# Sch_Kur.net
KiCad netlist of a schematic drawn in Altium Designer
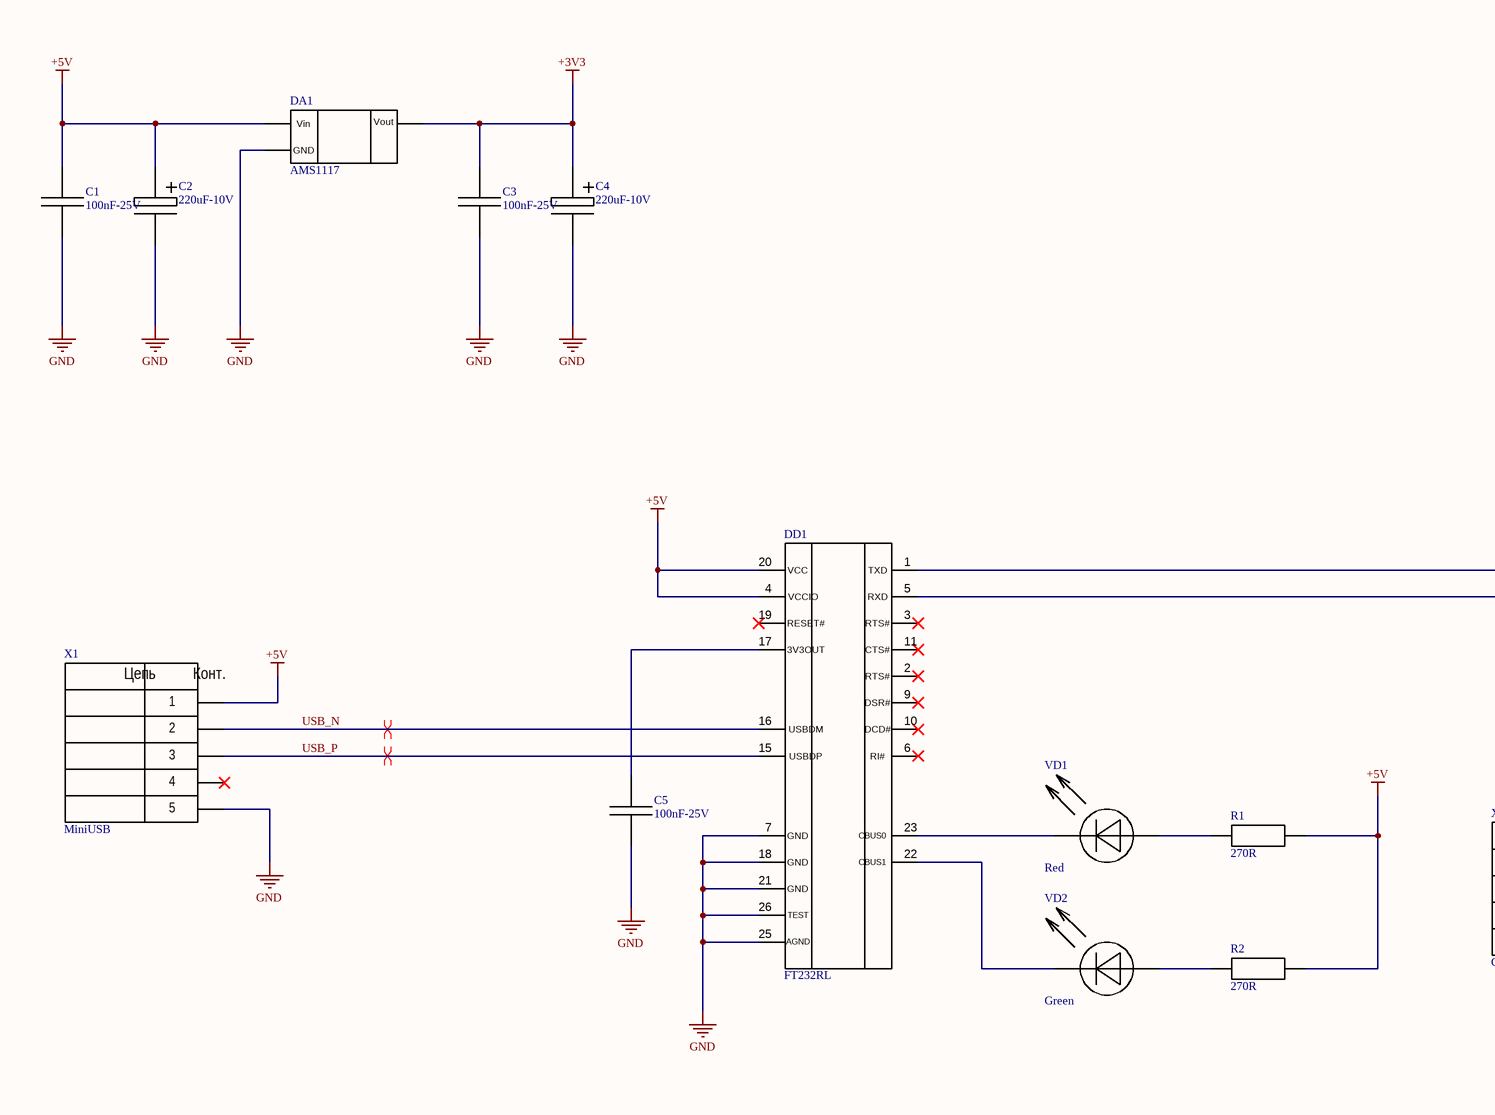
[diagram p0: Sch_Kur.SchDoc, left]
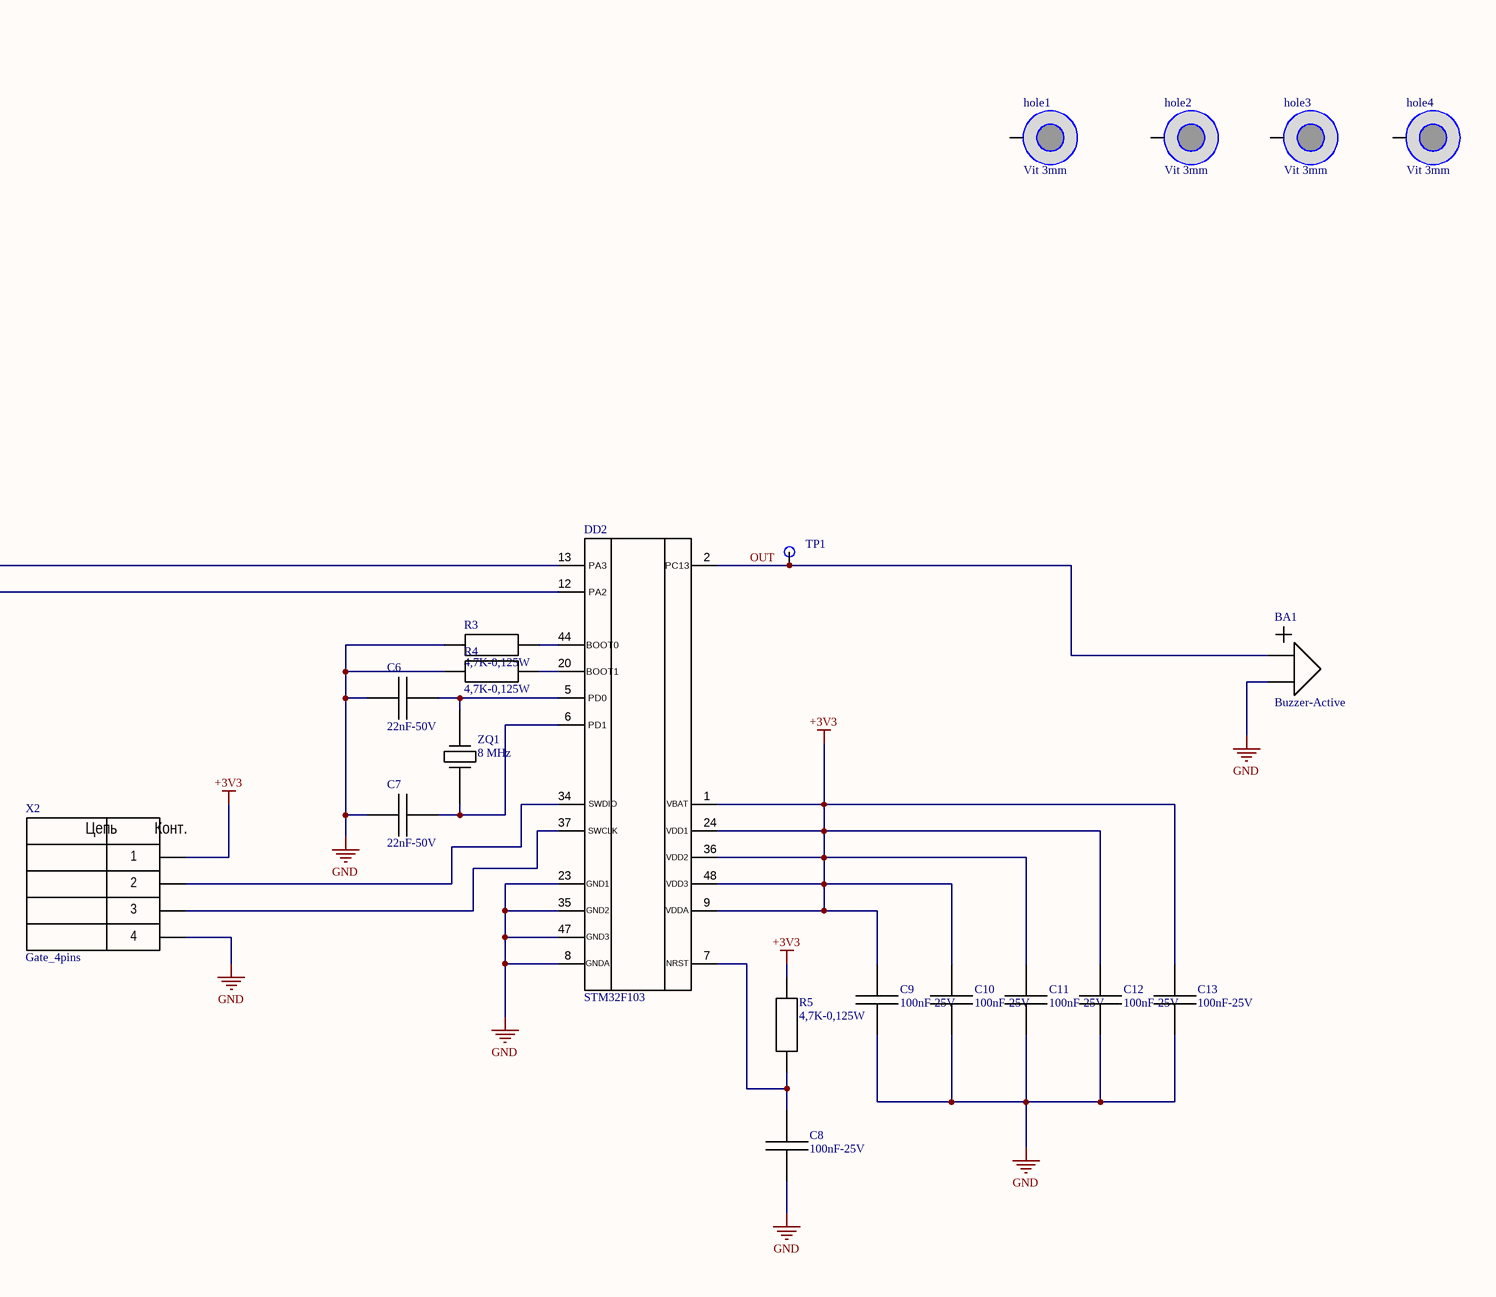
[diagram p1: Sch_Kur.SchDoc, right]

(export (version "E")
  (design (tool "Eeschema 10.0.6"))
  (components
    (comp (ref "BA1")
      (value "Buzzer-Active")
      (footprint "28# Buzzer MINI")
      (libsource (lib "Schlib_Kur") (part "Buzzer"))
    )
    (comp (ref "C1")
      (value "100nF-25V")
      (footprint "Cap Ceramic 0603 SMD")
      (libsource (lib "Schlib_Kur") (part "Cap_100nF"))
    )
    (comp (ref "C2")
      (value "220uF-10V")
      (footprint "CAP ALU CASE E SMD")
      (libsource (lib "Schlib_Kur") (part "ECAP_220uF"))
    )
    (comp (ref "C3")
      (value "100nF-25V")
      (footprint "Cap Ceramic 0603 SMD")
      (libsource (lib "Schlib_Kur") (part "Cap_100nF"))
    )
    (comp (ref "C4")
      (value "220uF-10V")
      (footprint "CAP ALU CASE E SMD")
      (libsource (lib "Schlib_Kur") (part "ECAP_220uF"))
    )
    (comp (ref "C5")
      (value "100nF-25V")
      (footprint "Cap Ceramic 0603 SMD")
      (libsource (lib "Schlib_Kur") (part "Cap_100nF"))
    )
    (comp (ref "C6")
      (value "22nF-50V")
      (footprint "Cap Ceramic 0805 SMD")
      (libsource (lib "Schlib_Kur") (part "Cap_22nF"))
    )
    (comp (ref "C7")
      (value "22nF-50V")
      (footprint "Cap Ceramic 0805 SMD")
      (libsource (lib "Schlib_Kur") (part "Cap_22nF"))
    )
    (comp (ref "C8")
      (value "100nF-25V")
      (footprint "Cap Ceramic 0603 SMD")
      (libsource (lib "Schlib_Kur") (part "Cap_100nF"))
    )
    (comp (ref "C9")
      (value "100nF-25V")
      (footprint "Cap Ceramic 0603 SMD")
      (libsource (lib "Schlib_Kur") (part "Cap_100nF"))
    )
    (comp (ref "C10")
      (value "100nF-25V")
      (footprint "Cap Ceramic 0603 SMD")
      (libsource (lib "Schlib_Kur") (part "Cap_100nF"))
    )
    (comp (ref "C11")
      (value "100nF-25V")
      (footprint "Cap Ceramic 0603 SMD")
      (libsource (lib "Schlib_Kur") (part "Cap_100nF"))
    )
    (comp (ref "C12")
      (value "100nF-25V")
      (footprint "Cap Ceramic 0603 SMD")
      (libsource (lib "Schlib_Kur") (part "Cap_100nF"))
    )
    (comp (ref "C13")
      (value "100nF-25V")
      (footprint "Cap Ceramic 0603 SMD")
      (libsource (lib "Schlib_Kur") (part "Cap_100nF"))
    )
    (comp (ref "DA1")
      (value "AMS1117")
      (footprint "AMS1117-3.3V")
      (libsource (lib "Schlib_Kur") (part "AMS1117-3.3"))
    )
    (comp (ref "DD1") (value "FT232RL") (footprint "SSOP 28") (libsource (lib "Schlib_Kur") (part "FT232RL")))
    (comp (ref "DD2")
      (value "STM32F103")
      (footprint "stm32f103c8t6-48LQFP")
      (libsource (lib "Schlib_Kur") (part "STM32F103C8T6"))
    )
    (comp (ref "hole1")
      (value "Vit 3mm")
      (footprint "Screw 3 small")
      (libsource (lib "lpson") (part "Vit 3mm"))
    )
    (comp (ref "hole2")
      (value "Vit 3mm")
      (footprint "Screw 3 small")
      (libsource (lib "lpson") (part "Vit 3mm"))
    )
    (comp (ref "hole3")
      (value "Vit 3mm")
      (footprint "Screw 3 small")
      (libsource (lib "lpson") (part "Vit 3mm"))
    )
    (comp (ref "hole4")
      (value "Vit 3mm")
      (footprint "Screw 3 small")
      (libsource (lib "lpson") (part "Vit 3mm"))
    )
    (comp (ref "R1") (value "270R") (footprint "Res 0805 SMD") (libsource (lib "") (part "Res_270_1")))
    (comp (ref "R2")
      (value "270R")
      (footprint "Res 0805 SMD")
      (libsource (lib "Schlib_Kur") (part "Res_270"))
    )
    (comp (ref "R3")
      (value "4,7K-0,125W")
      (footprint "Res 0805 SMD")
      (libsource (lib "Schlib_Kur") (part "Res_4K7"))
    )
    (comp (ref "R4")
      (value "4,7K-0,125W")
      (footprint "Res 0805 SMD")
      (libsource (lib "Schlib_Kur") (part "Res_4K7"))
    )
    (comp (ref "R5")
      (value "4,7K-0,125W")
      (footprint "Res 0805 SMD")
      (libsource (lib "Schlib_Kur") (part "Res_4K7"))
    )
    (comp (ref "TP1") (value "TP1") (footprint "TP1") (libsource (lib "Schlib_Kur") (part "Test_point")))
    (comp (ref "VD1") (value "Red") (footprint "Led 0805R") (libsource (lib "Schlib_Kur") (part "LED_red")))
    (comp (ref "VD2")
      (value "Green")
      (footprint "Led 0805G")
      (libsource (lib "Schlib_Kur") (part "LED_green"))
    )
    (comp (ref "X1")
      (value "MiniUSB")
      (footprint "USB_MNI_B")
      (libsource (lib "Schlib_Kur") (part "Mini_USB"))
    )
    (comp (ref "X2")
      (value "Gate_4pins")
      (footprint "Header_4")
      (libsource (lib "Schlib_Kur") (part "Gate_4pins"))
    )
    (comp (ref "ZQ1")
      (value "8 MHz")
      (footprint "CRYSTAL-HC49S")
      (libsource (lib "Schlib_Kur") (part "Quartz resonator_8MHz"))
    )
  )
  (nets
    (net (code "1") (name "+3V3") (class "Default")
      (node (ref "C10") (pin "2") (pinfunction "2_2") (pintype "passive"))
      (node (ref "C11") (pin "2") (pinfunction "2_2") (pintype "passive"))
      (node (ref "C12") (pin "2") (pinfunction "2_2") (pintype "passive"))
      (node (ref "C13") (pin "2") (pinfunction "2_2") (pintype "passive"))
      (node (ref "C3") (pin "2") (pinfunction "2_2") (pintype "passive"))
      (node (ref "C4") (pin "1") (pinfunction "1_1") (pintype "passive"))
      (node (ref "C9") (pin "2") (pinfunction "2_2") (pintype "passive"))
      (node (ref "DA1") (pin "2") (pinfunction "2_2") (pintype "passive"))
      (node (ref "DD2") (pin "1") (pinfunction "1_1") (pintype "passive"))
      (node (ref "DD2") (pin "24") (pinfunction "24_24") (pintype "passive"))
      (node (ref "DD2") (pin "36") (pinfunction "36_36") (pintype "passive"))
      (node (ref "DD2") (pin "48") (pinfunction "48_48") (pintype "passive"))
      (node (ref "DD2") (pin "9") (pinfunction "9_9") (pintype "passive"))
      (node (ref "R5") (pin "2") (pinfunction "2_2") (pintype "passive"))
      (node (ref "X2") (pin "1") (pintype "passive"))
    )
    (net (code "2") (name "+5V") (class "Default")
      (node (ref "C1") (pin "2") (pinfunction "2_2") (pintype "passive"))
      (node (ref "C2") (pin "1") (pinfunction "1_1") (pintype "passive"))
      (node (ref "DA1") (pin "3") (pinfunction "3_3") (pintype "passive"))
      (node (ref "DD1") (pin "20") (pinfunction "20_20") (pintype "passive"))
      (node (ref "DD1") (pin "4") (pinfunction "4_4") (pintype "passive"))
      (node (ref "R1") (pin "2") (pinfunction "2_2") (pintype "passive"))
      (node (ref "R2") (pin "1") (pinfunction "1_1") (pintype "passive"))
      (node (ref "X1") (pin "1") (pinfunction "1_1") (pintype "passive"))
    )
    (net (code "3") (name "/OUT") (class "Default")
      (node (ref "BA1") (pin "1") (pinfunction "1_1") (pintype "passive"))
      (node (ref "DD2") (pin "2") (pinfunction "2_2") (pintype "passive"))
      (node (ref "TP1") (pin "1") (pinfunction "1_1") (pintype "passive"))
    )
    (net (code "4") (name "/USB_N") (class "Default")
      (node (ref "DD1") (pin "16") (pinfunction "16_16") (pintype "passive"))
      (node (ref "X1") (pin "2") (pinfunction "2_2") (pintype "passive"))
    )
    (net (code "5") (name "/USB_P") (class "Default")
      (node (ref "DD1") (pin "15") (pinfunction "15_15") (pintype "passive"))
      (node (ref "X1") (pin "3") (pinfunction "3_3") (pintype "passive"))
    )
    (net (code "6") (name "GND") (class "Default")
      (node (ref "BA1") (pin "2") (pinfunction "2_2") (pintype "passive"))
      (node (ref "C1") (pin "1") (pinfunction "1_1") (pintype "passive"))
      (node (ref "C10") (pin "1") (pinfunction "1_1") (pintype "passive"))
      (node (ref "C11") (pin "1") (pinfunction "1_1") (pintype "passive"))
      (node (ref "C12") (pin "1") (pinfunction "1_1") (pintype "passive"))
      (node (ref "C13") (pin "1") (pinfunction "1_1") (pintype "passive"))
      (node (ref "C2") (pin "2") (pinfunction "2_2") (pintype "passive"))
      (node (ref "C3") (pin "1") (pinfunction "1_1") (pintype "passive"))
      (node (ref "C4") (pin "2") (pinfunction "2_2") (pintype "passive"))
      (node (ref "C5") (pin "1") (pinfunction "1_1") (pintype "passive"))
      (node (ref "C6") (pin "1") (pinfunction "1_1") (pintype "passive"))
      (node (ref "C7") (pin "1") (pinfunction "1_1") (pintype "passive"))
      (node (ref "C8") (pin "1") (pinfunction "1_1") (pintype "passive"))
      (node (ref "C9") (pin "1") (pinfunction "1_1") (pintype "passive"))
      (node (ref "DA1") (pin "1") (pinfunction "1_1") (pintype "passive"))
      (node (ref "DD1") (pin "18") (pinfunction "18_18") (pintype "passive"))
      (node (ref "DD1") (pin "21") (pinfunction "21_21") (pintype "passive"))
      (node (ref "DD1") (pin "25") (pinfunction "25_25") (pintype "passive"))
      (node (ref "DD1") (pin "26") (pinfunction "26_26") (pintype "passive"))
      (node (ref "DD1") (pin "7") (pinfunction "7_7") (pintype "passive"))
      (node (ref "DD2") (pin "23") (pinfunction "23_23") (pintype "passive"))
      (node (ref "DD2") (pin "35") (pinfunction "35_35") (pintype "passive"))
      (node (ref "DD2") (pin "47") (pinfunction "47_47") (pintype "passive"))
      (node (ref "DD2") (pin "8") (pinfunction "8_8") (pintype "passive"))
      (node (ref "R3") (pin "1") (pinfunction "1_1") (pintype "passive"))
      (node (ref "R4") (pin "1") (pinfunction "1_1") (pintype "passive"))
      (node (ref "X1") (pin "5") (pinfunction "5_5") (pintype "passive"))
      (node (ref "X2") (pin "4") (pintype "passive"))
    )
    (net (code "7") (name "Net-(C5-Pad2)") (class "Default")
      (node (ref "C5") (pin "2") (pinfunction "2_2") (pintype "passive"))
      (node (ref "DD1") (pin "17") (pinfunction "17_17") (pintype "passive"))
    )
    (net (code "8") (name "Net-(C6-Pad2)") (class "Default")
      (node (ref "C6") (pin "2") (pinfunction "2_2") (pintype "passive"))
      (node (ref "DD2") (pin "5") (pinfunction "5_5") (pintype "passive"))
      (node (ref "ZQ1") (pin "2") (pinfunction "2_2") (pintype "passive"))
    )
    (net (code "9") (name "Net-(C7-Pad2)") (class "Default")
      (node (ref "C7") (pin "2") (pinfunction "2_2") (pintype "passive"))
      (node (ref "DD2") (pin "6") (pinfunction "6_6") (pintype "passive"))
      (node (ref "ZQ1") (pin "1") (pinfunction "1_1") (pintype "passive"))
    )
    (net (code "10") (name "Net-(C8-Pad2)") (class "Default")
      (node (ref "C8") (pin "2") (pinfunction "2_2") (pintype "passive"))
      (node (ref "DD2") (pin "7") (pinfunction "7_7") (pintype "passive"))
      (node (ref "R5") (pin "1") (pinfunction "1_1") (pintype "passive"))
    )
    (net (code "11") (name "Net-(DD1-Pad1)") (class "Default")
      (node (ref "DD1") (pin "1") (pinfunction "1_1") (pintype "passive"))
      (node (ref "DD2") (pin "13") (pinfunction "13_13") (pintype "passive"))
    )
    (net (code "12") (name "Net-(DD1-Pad5)") (class "Default")
      (node (ref "DD1") (pin "5") (pinfunction "5_5") (pintype "passive"))
      (node (ref "DD2") (pin "12") (pinfunction "12_12") (pintype "passive"))
    )
    (net (code "13") (name "Net-(DD1-Pad22)") (class "Default")
      (node (ref "DD1") (pin "22") (pinfunction "22_22") (pintype "passive"))
      (node (ref "VD2") (pin "2") (pinfunction "2_2") (pintype "passive"))
    )
    (net (code "14") (name "Net-(DD1-Pad23)") (class "Default")
      (node (ref "DD1") (pin "23") (pinfunction "23_23") (pintype "passive"))
      (node (ref "VD1") (pin "2") (pinfunction "2_2") (pintype "passive"))
    )
    (net (code "15") (name "Net-(DD2-Pad20)") (class "Default")
      (node (ref "DD2") (pin "20") (pinfunction "20_20") (pintype "passive"))
      (node (ref "R4") (pin "2") (pinfunction "2_2") (pintype "passive"))
    )
    (net (code "16") (name "Net-(DD2-Pad34)") (class "Default")
      (node (ref "DD2") (pin "34") (pinfunction "34_34") (pintype "passive"))
      (node (ref "X2") (pin "2") (pintype "passive"))
    )
    (net (code "17") (name "Net-(DD2-Pad37)") (class "Default")
      (node (ref "DD2") (pin "37") (pinfunction "37_37") (pintype "passive"))
      (node (ref "X2") (pin "3") (pintype "passive"))
    )
    (net (code "18") (name "Net-(DD2-Pad44)") (class "Default")
      (node (ref "DD2") (pin "44") (pinfunction "44_44") (pintype "passive"))
      (node (ref "R3") (pin "2") (pinfunction "2_2") (pintype "passive"))
    )
    (net (code "19") (name "Net-(R1-Pad1)") (class "Default")
      (node (ref "R1") (pin "1") (pinfunction "1_1") (pintype "passive"))
      (node (ref "VD1") (pin "1") (pinfunction "1_1") (pintype "passive"))
    )
    (net (code "20") (name "Net-(R2-Pad2)") (class "Default")
      (node (ref "R2") (pin "2") (pinfunction "2_2") (pintype "passive"))
      (node (ref "VD2") (pin "1") (pinfunction "1_1") (pintype "passive"))
    )
    (net (code "21") (name "unconnected-(DD1-Pad2)") (class "Default")
      (node (ref "DD1") (pin "2") (pinfunction "2_2") (pintype "passive+no_connect"))
    )
    (net (code "22") (name "unconnected-(DD1-Pad3)") (class "Default")
      (node (ref "DD1") (pin "3") (pinfunction "3_3") (pintype "passive+no_connect"))
    )
    (net (code "23") (name "unconnected-(DD1-Pad6)") (class "Default")
      (node (ref "DD1") (pin "6") (pinfunction "6_6") (pintype "passive+no_connect"))
    )
    (net (code "24") (name "unconnected-(DD1-Pad9)") (class "Default")
      (node (ref "DD1") (pin "9") (pinfunction "9_9") (pintype "passive+no_connect"))
    )
    (net (code "25") (name "unconnected-(DD1-Pad10)") (class "Default")
      (node (ref "DD1") (pin "10") (pinfunction "10_10") (pintype "passive+no_connect"))
    )
    (net (code "26") (name "unconnected-(DD1-Pad11)") (class "Default")
      (node (ref "DD1") (pin "11") (pinfunction "11_11") (pintype "passive+no_connect"))
    )
    (net (code "27") (name "unconnected-(DD1-Pad19)") (class "Default")
      (node (ref "DD1") (pin "19") (pinfunction "19_19") (pintype "passive+no_connect"))
    )
    (net (code "28") (name "unconnected-(X1-Pad4)") (class "Default")
      (node (ref "X1") (pin "4") (pinfunction "4_4") (pintype "passive+no_connect"))
    )
    (net (code "29") (name "unconnected-(hole1-hole-Pad1)") (class "Default")
      (node (ref "hole1") (pin "1") (pinfunction "hole_1") (pintype "passive"))
    )
    (net (code "30") (name "unconnected-(hole2-hole-Pad1)") (class "Default")
      (node (ref "hole2") (pin "1") (pinfunction "hole_1") (pintype "passive"))
    )
    (net (code "31") (name "unconnected-(hole3-hole-Pad1)") (class "Default")
      (node (ref "hole3") (pin "1") (pinfunction "hole_1") (pintype "passive"))
    )
    (net (code "32") (name "unconnected-(hole4-hole-Pad1)") (class "Default")
      (node (ref "hole4") (pin "1") (pinfunction "hole_1") (pintype "passive"))
    )
  )
)
